# power.net
KiCad netlist of a schematic drawn in Altium Designer
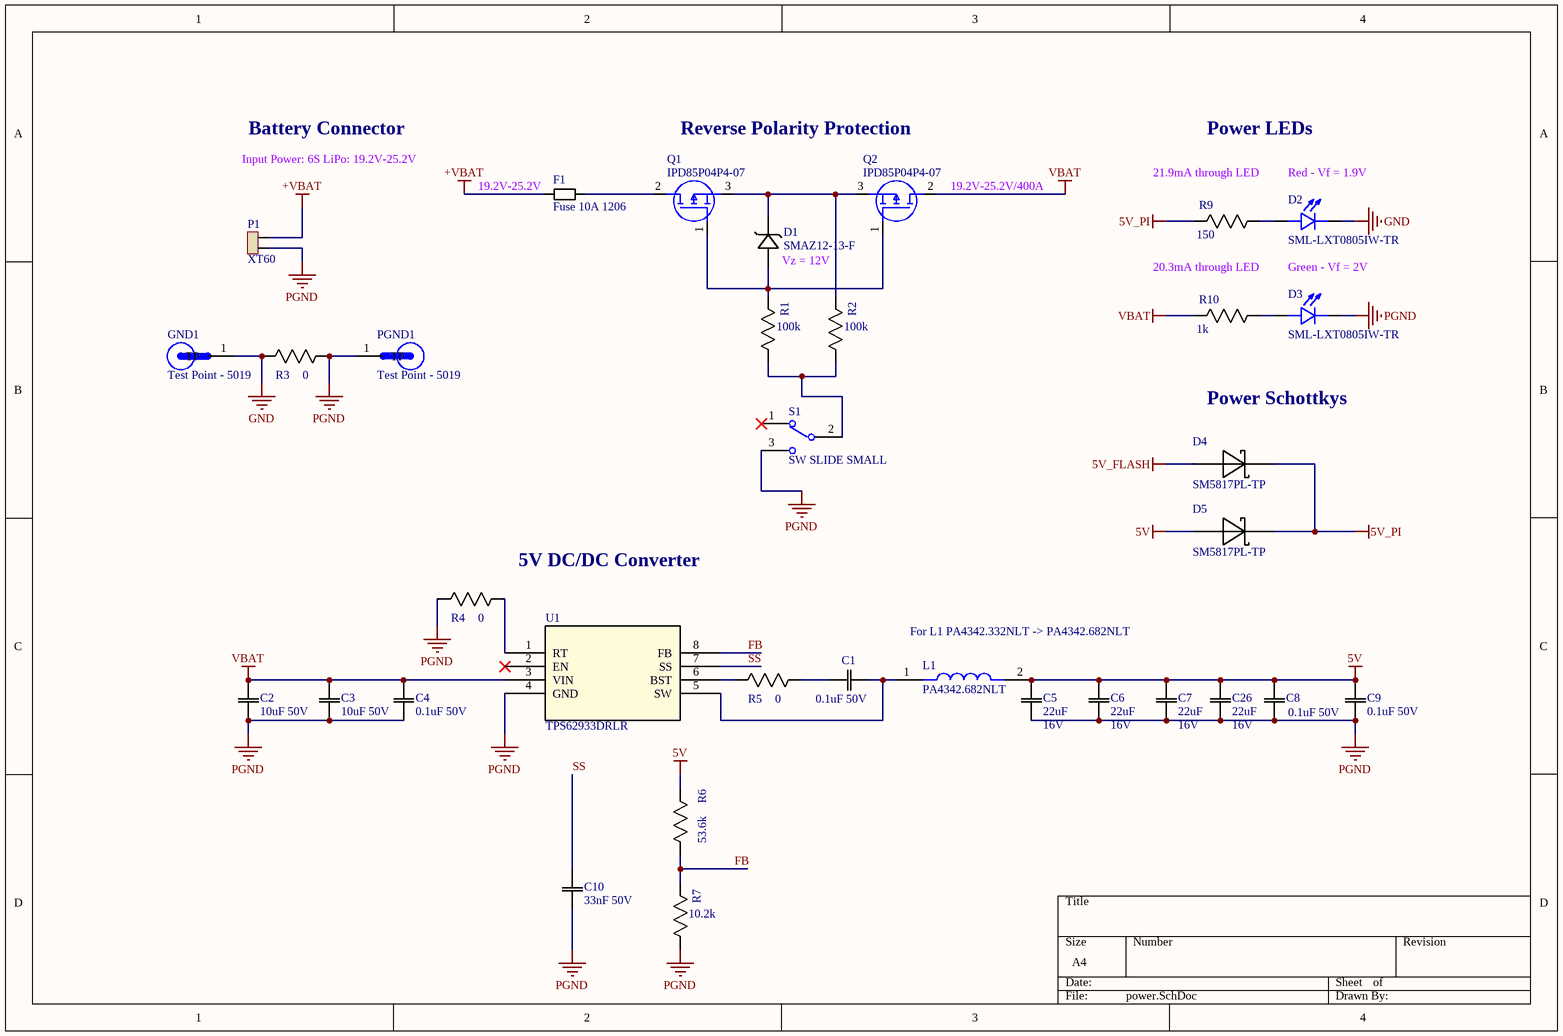
[diagram p0: power.SchDoc]

(export (version "E")
  (design (tool "Eeschema 10.0.6"))
  (components
    (comp (ref "C1")
      (value "0.1uF 50V")
      (footprint "0805")
      (description "Default Symbol for Capacitors")
      (fields (field (name "PART NUMBER") "CAP 10uF 50V") (field (name "TOLERANCE") "10%"))
      (libsource (lib "capacitor_library") (part "CAP_Default"))
    )
    (comp (ref "C2")
      (value "10uF 50V")
      (footprint "0805")
      (description "Default Symbol for Capacitors")
      (fields (field (name "PART NUMBER") "CAP 10uF 50V") (field (name "TOLERANCE") "10%"))
      (libsource (lib "capacitor_library") (part "CAP_Default"))
    )
    (comp (ref "C3")
      (value "10uF 50V")
      (footprint "0805")
      (description "Default Symbol for Capacitors")
      (fields (field (name "PART NUMBER") "CAP 10uF 50V") (field (name "TOLERANCE") "10%"))
      (libsource (lib "capacitor_library") (part "CAP_Default"))
    )
    (comp (ref "C4")
      (value "0.1uF 50V")
      (footprint "0805")
      (description "Default Symbol for Capacitors")
      (fields (field (name "PART NUMBER") "CAP 10uF 50V") (field (name "TOLERANCE") "10%"))
      (libsource (lib "capacitor_library") (part "CAP_Default"))
    )
    (comp (ref "C5")
      (value "22uF")
      (footprint "0805")
      (description "CAP CER 22UF 16V X5R 0805")
      (fields
        (field (name "TOLERANCE") "10%")
        (field (name "RATING") "16V")
        (field (name "PART NUMBER") "CAP 22uF 16V")
      )
      (libsource (lib "capacitor_library") (part "CAP 22uF 16V"))
    )
    (comp (ref "C6")
      (value "22uF")
      (footprint "0805")
      (description "CAP CER 22UF 16V X5R 0805")
      (fields
        (field (name "TOLERANCE") "10%")
        (field (name "RATING") "16V")
        (field (name "PART NUMBER") "CAP 22uF 16V")
      )
      (libsource (lib "capacitor_library") (part "CAP 22uF 16V"))
    )
    (comp (ref "C7")
      (value "22uF")
      (footprint "0805")
      (description "CAP CER 22UF 16V X5R 0805")
      (fields
        (field (name "TOLERANCE") "10%")
        (field (name "RATING") "16V")
        (field (name "PART NUMBER") "CAP 22uF 16V")
      )
      (libsource (lib "capacitor_library") (part "CAP 22uF 16V"))
    )
    (comp (ref "C8")
      (value "0.1uF 50V")
      (footprint "0805")
      (description "Default Symbol for Capacitors")
      (fields (field (name "PART NUMBER") "CAP 10uF 50V") (field (name "TOLERANCE") "10%"))
      (libsource (lib "capacitor_library") (part "CAP_Default"))
    )
    (comp (ref "C9")
      (value "0.1uF 50V")
      (footprint "0805")
      (description "Default Symbol for Capacitors")
      (fields (field (name "PART NUMBER") "CAP 10uF 50V") (field (name "TOLERANCE") "10%"))
      (libsource (lib "capacitor_library") (part "CAP_Default"))
    )
    (comp (ref "C10")
      (value "33nF 50V")
      (footprint "0805")
      (description "Default Symbol for Capacitors")
      (fields (field (name "PART NUMBER") "CAP 33nF 50V") (field (name "TOLERANCE") "5%"))
      (libsource (lib "capacitor_library") (part "CAP_Default"))
    )
    (comp (ref "C26")
      (value "22uF")
      (footprint "0805")
      (description "CAP CER 22UF 16V X5R 0805")
      (fields
        (field (name "TOLERANCE") "10%")
        (field (name "RATING") "16V")
        (field (name "PART NUMBER") "CAP 22uF 16V")
      )
      (libsource (lib "capacitor_library") (part "CAP 22uF 16V"))
    )
    (comp (ref "D1")
      (value "SMAZ12-13-F")
      (footprint "SMA_DIO-L")
      (description "Zener Diode 12 V 1 W ±5% Surface Mount SMA")
      (fields
        (field (name "PART NUMBER") "DIODE ZENER 12V 1W")
        (field (name "COPYRIGHT") "Copyright (C) 2021 Ultra Librarian. All rights reserved.")
      )
      (libsource (lib "Diode_Library") (part "DIODE ZENER 12V 1W"))
    )
    (comp (ref "D2")
      (value "SML-LXT0805IW-TR")
      (footprint "LEDC2012X120N")
      (fields (field (name "MF") "Lumex Opto/Components"))
      (libsource (lib "SML-LXT0805IW-TR") (part "SML-LXT0805IW-TR"))
    )
    (comp (ref "D3")
      (value "SML-LXT0805IW-TR")
      (footprint "LEDC2012X120N")
      (fields (field (name "MF") "Lumex Opto/Components"))
      (libsource (lib "SML-LXT0805IW-TR") (part "SML-LXT0805IW-TR"))
    )
    (comp (ref "D4")
      (value "SM5817PL-TP")
      (footprint "SOD-123")
      (description "Diode Schottky 20V 1A Surface Mount SOD-123FL")
      (fields (field (name "MF") "Micro Commercial Co") (field (name "PART NUMBER") "DIODE SCHOTTKY 20V 1A"))
      (libsource (lib "Diode_Library") (part "DIODE SCHOTTKY 20V 1A"))
    )
    (comp (ref "D5")
      (value "SM5817PL-TP")
      (footprint "SOD-123")
      (description "Diode Schottky 20V 1A Surface Mount SOD-123FL")
      (fields (field (name "MF") "Micro Commercial Co") (field (name "PART NUMBER") "DIODE SCHOTTKY 20V 1A"))
      (libsource (lib "Diode_Library") (part "DIODE SCHOTTKY 20V 1A"))
    )
    (comp (ref "F1")
      (value "Fuse 10A 1206")
      (footprint "1206")
      (description "FUSE 10A 32V AC 63V DC 1206")
      (fields (field (name "PART NUMBER") "FUSE 10A 63V SLOW"))
      (libsource (lib "Fuse_Library") (part "FUSE 10A 63V SLOW"))
    )
    (comp (ref "GND1")
      (value "Test Point - 5019")
      (footprint "TP380X203")
      (description "PC Test Point, Miniature Phosphor Bronze, Silver Plating Surface Mount Mounting Type")
      (fields (field (name "MP") "5019") (field (name "MF") "Keystone Electronics"))
      (libsource (lib "IC_Library") (part "Test Point - 5019"))
    )
    (comp (ref "L1")
      (value "PA4342.682NLT")
      (footprint "IND_PA4342.332NLT")
      (description "FIXED IND 6.8UH 8.5A 23.3MOHM SM")
      (fields (field (name "MF") "Pulse") (field (name "MP") "PA4342.332NLT"))
      (libsource (lib "PA4342.332NLT") (part "PA4342.332NLT"))
    )
    (comp (ref "P1")
      (value "XT60")
      (footprint "Amass_XT60PW-M")
      (description "XT60 CONNECTORS FEMALE PAIR")
      (fields (field (name "MF") "SparkFun Electronics") (field (name "MP") "PRT-10474"))
      (libsource (lib "Connector_Library") (part "XT60 Connector"))
    )
    (comp (ref "PGND1")
      (value "Test Point - 5019")
      (footprint "TP380X203")
      (description "PC Test Point, Miniature Phosphor Bronze, Silver Plating Surface Mount Mounting Type")
      (fields (field (name "MP") "5019") (field (name "MF") "Keystone Electronics"))
      (libsource (lib "IC_Library") (part "Test Point - 5019"))
    )
    (comp (ref "Q1")
      (value "IPD85P04P4-07")
      (footprint "DPAK (TO-252)")
      (description "P-Channel 40 V 85A (Tc) 88W (Tc) Surface Mount PG-TO252-3-313")
      (fields (field (name "PART NUMBER") "MOSFET IPD85P04P4-07"))
      (libsource (lib "Transistor_Library") (part "MOSFET IPD85P04P4-07"))
    )
    (comp (ref "Q2")
      (value "IPD85P04P4-07")
      (footprint "DPAK (TO-252)")
      (description "P-Channel 40 V 85A (Tc) 88W (Tc) Surface Mount PG-TO252-3-313")
      (fields (field (name "PART NUMBER") "MOSFET IPD85P04P4-07"))
      (libsource (lib "Transistor_Library") (part "MOSFET IPD85P04P4-07"))
    )
    (comp (ref "R1")
      (value "100k")
      (footprint "0805")
      (description "Default Resistor Symbol")
      (fields (field (name "TOLERANCE") "1%") (field (name "PART NUMBER") "RES 100k 1/8W - 1%"))
      (libsource (lib "") (part "RES_DEFAULT_1"))
    )
    (comp (ref "R2")
      (value "100k")
      (footprint "0805")
      (description "Default Resistor Symbol")
      (fields (field (name "TOLERANCE") "1%") (field (name "PART NUMBER") "RES 100k 1/8W - 1%"))
      (libsource (lib "") (part "RES_DEFAULT_1"))
    )
    (comp (ref "R3")
      (value "0")
      (footprint "0805")
      (description "Default Resistor Symbol")
      (fields (field (name "PART NUMBER") "RES 0 JUMPER 0603"))
      (libsource (lib "Resistor_Library") (part "RES_DEFAULT"))
    )
    (comp (ref "R4")
      (value "0")
      (footprint "0805")
      (description "Default Resistor Symbol")
      (fields (field (name "PART NUMBER") "RES 0 JUMPER 0603"))
      (libsource (lib "Resistor_Library") (part "RES_DEFAULT"))
    )
    (comp (ref "R5")
      (value "0")
      (footprint "0805")
      (description "Default Resistor Symbol")
      (fields (field (name "PART NUMBER") "RES 0 JUMPER 0603"))
      (libsource (lib "") (part "RES_DEFAULT_1"))
    )
    (comp (ref "R6")
      (value "53.6k")
      (footprint "0805")
      (description "Default Resistor Symbol")
      (fields (field (name "TOLERANCE") "5%") (field (name "PART NUMBER") "RES 56.2k 1/10W"))
      (libsource (lib "") (part "RES_DEFAULT_2"))
    )
    (comp (ref "R7")
      (value "10.2k")
      (footprint "0805")
      (description "Default Resistor Symbol")
      (fields (field (name "TOLERANCE") "5%") (field (name "PART NUMBER") "RES 10.2k 1/8W"))
      (libsource (lib "Resistor_Library") (part "RES_DEFAULT"))
    )
    (comp (ref "R9")
      (value "150")
      (footprint "0805")
      (description "Default Resistor Symbol")
      (fields (field (name "TOLERANCE") "5%") (field (name "PART NUMBER") "RES 150.0 1/8W"))
      (libsource (lib "") (part "RES_DEFAULT_1"))
    )
    (comp (ref "R10")
      (value "1k")
      (footprint "0805")
      (description "Default Resistor Symbol")
      (fields (field (name "TOLERANCE") "5%") (field (name "PART NUMBER") "RES 1.1k 1/8W"))
      (libsource (lib "Resistor_Library") (part "RES_DEFAULT"))
    )
    (comp (ref "S1")
      (value "SW SLIDE SMALL")
      (footprint "SW SLIDE SMALL")
      (description "Slide Switch SPDT Surface Mount, Right Angle")
      (fields (field (name "MF") "C&K") (field (name "MP") "JS102011SAQN"))
      (libsource (lib "Switch_Library") (part "SW SLIDE SMALL"))
    )
    (comp (ref "U1")
      (value "TPS62933DRLR")
      (footprint "SOT_33DRLR_TEX")
      (description "No Description Available")
      (libsource (lib "XTPS62933DRLR") (part "XTPS62933DRLR"))
    )
  )
  (nets
    (net (code "1") (name "+VBAT") (class "Default")
      (node (ref "F1") (pin "1") (pinfunction "1_1") (pintype "passive"))
      (node (ref "P1") (pin "2") (pinfunction "2_2") (pintype "passive"))
    )
    (net (code "2") (name "/FB") (class "Default")
      (node (ref "R6") (pin "1") (pinfunction "R1_1") (pintype "passive"))
      (node (ref "R7") (pin "2") (pinfunction "R2_2") (pintype "passive"))
      (node (ref "U1") (pin "8") (pinfunction "FB_8") (pintype "passive"))
    )
    (net (code "3") (name "/SS") (class "Default")
      (node (ref "C10") (pin "2") (pinfunction "C2_2") (pintype "passive"))
      (node (ref "U1") (pin "7") (pinfunction "SS_7") (pintype "passive"))
    )
    (net (code "4") (name "5V") (class "Default")
      (node (ref "C26") (pin "2") (pinfunction "C2_2") (pintype "passive"))
      (node (ref "C5") (pin "2") (pinfunction "C2_2") (pintype "passive"))
      (node (ref "C6") (pin "2") (pinfunction "C2_2") (pintype "passive"))
      (node (ref "C7") (pin "2") (pinfunction "C2_2") (pintype "passive"))
      (node (ref "C8") (pin "2") (pinfunction "C2_2") (pintype "passive"))
      (node (ref "C9") (pin "2") (pinfunction "C2_2") (pintype "passive"))
      (node (ref "D5") (pin "A") (pinfunction "A_A") (pintype "passive"))
      (node (ref "L1") (pin "2") (pinfunction "2_2") (pintype "passive"))
      (node (ref "R6") (pin "2") (pinfunction "R2_2") (pintype "passive"))
    )
    (net (code "5") (name "5V_FLASH") (class "Default")
      (node (ref "D4") (pin "A") (pinfunction "A_A") (pintype "passive"))
    )
    (net (code "6") (name "5V_PI") (class "Default")
      (node (ref "D4") (pin "C") (pinfunction "K_C") (pintype "passive"))
      (node (ref "D5") (pin "C") (pinfunction "K_C") (pintype "passive"))
      (node (ref "R9") (pin "2") (pinfunction "R2_2") (pintype "passive"))
    )
    (net (code "7") (name "GND") (class "Default")
      (node (ref "D2") (pin "C") (pinfunction "C_C") (pintype "passive"))
      (node (ref "GND1") (pin "1") (pinfunction "TP_1") (pintype "passive"))
      (node (ref "R3") (pin "2") (pinfunction "R2_2") (pintype "passive"))
    )
    (net (code "8") (name "Net-(C1-C1)") (class "Default")
      (node (ref "C1") (pin "1") (pinfunction "C1_1") (pintype "passive"))
      (node (ref "L1") (pin "1") (pinfunction "1_1") (pintype "passive"))
      (node (ref "U1") (pin "5") (pinfunction "SW_5") (pintype "passive"))
    )
    (net (code "9") (name "Net-(C1-C2)") (class "Default")
      (node (ref "C1") (pin "2") (pinfunction "C2_2") (pintype "passive"))
      (node (ref "R5") (pin "1") (pinfunction "R1_1") (pintype "passive"))
    )
    (net (code "10") (name "Net-(Q1-D)") (class "Default")
      (node (ref "F1") (pin "2") (pinfunction "2_2") (pintype "passive"))
      (node (ref "Q1") (pin "2") (pinfunction "D_2") (pintype "passive"))
    )
    (net (code "11") (name "Net-(Q1-G)") (class "Default")
      (node (ref "D1") (pin "2") (pinfunction "2_2") (pintype "passive"))
      (node (ref "Q1") (pin "1") (pinfunction "G_1") (pintype "passive"))
      (node (ref "Q2") (pin "1") (pinfunction "G_1") (pintype "passive"))
      (node (ref "R1") (pin "2") (pinfunction "R2_2") (pintype "passive"))
    )
    (net (code "12") (name "Net-(Q1-S)") (class "Default")
      (node (ref "D1") (pin "1") (pinfunction "1_1") (pintype "passive"))
      (node (ref "Q1") (pin "3") (pinfunction "S_3") (pintype "passive"))
      (node (ref "Q2") (pin "3") (pinfunction "S_3") (pintype "passive"))
      (node (ref "R2") (pin "2") (pinfunction "R2_2") (pintype "passive"))
    )
    (net (code "13") (name "Net-(R1-R1)") (class "Default")
      (node (ref "R1") (pin "1") (pinfunction "R1_1") (pintype "passive"))
      (node (ref "R2") (pin "1") (pinfunction "R1_1") (pintype "passive"))
      (node (ref "S1") (pin "2") (pinfunction "2_2") (pintype "passive"))
    )
    (net (code "14") (name "Net-(R4-R1)") (class "Default")
      (node (ref "R4") (pin "1") (pinfunction "R1_1") (pintype "passive"))
      (node (ref "U1") (pin "1") (pinfunction "RT_1") (pintype "passive"))
    )
    (net (code "15") (name "Net-(R5-R2)") (class "Default")
      (node (ref "R5") (pin "2") (pinfunction "R2_2") (pintype "passive"))
      (node (ref "U1") (pin "6") (pinfunction "BST_6") (pintype "passive"))
    )
    (net (code "16") (name "Net-(R9-R1)") (class "Default")
      (node (ref "D2") (pin "A") (pinfunction "A_A") (pintype "passive"))
      (node (ref "R9") (pin "1") (pinfunction "R1_1") (pintype "passive"))
    )
    (net (code "17") (name "Net-(R10-R1)") (class "Default")
      (node (ref "D3") (pin "A") (pinfunction "A_A") (pintype "passive"))
      (node (ref "R10") (pin "1") (pinfunction "R1_1") (pintype "passive"))
    )
    (net (code "18") (name "PGND") (class "Default")
      (node (ref "C10") (pin "1") (pinfunction "C1_1") (pintype "passive"))
      (node (ref "C2") (pin "1") (pinfunction "C1_1") (pintype "passive"))
      (node (ref "C26") (pin "1") (pinfunction "C1_1") (pintype "passive"))
      (node (ref "C3") (pin "1") (pinfunction "C1_1") (pintype "passive"))
      (node (ref "C4") (pin "1") (pinfunction "C1_1") (pintype "passive"))
      (node (ref "C5") (pin "1") (pinfunction "C1_1") (pintype "passive"))
      (node (ref "C6") (pin "1") (pinfunction "C1_1") (pintype "passive"))
      (node (ref "C7") (pin "1") (pinfunction "C1_1") (pintype "passive"))
      (node (ref "C8") (pin "1") (pinfunction "C1_1") (pintype "passive"))
      (node (ref "C9") (pin "1") (pinfunction "C1_1") (pintype "passive"))
      (node (ref "D3") (pin "C") (pinfunction "C_C") (pintype "passive"))
      (node (ref "P1") (pin "1") (pinfunction "1_1") (pintype "passive"))
      (node (ref "PGND1") (pin "1") (pinfunction "TP_1") (pintype "passive"))
      (node (ref "R3") (pin "1") (pinfunction "R1_1") (pintype "passive"))
      (node (ref "R4") (pin "2") (pinfunction "R2_2") (pintype "passive"))
      (node (ref "R7") (pin "1") (pinfunction "R1_1") (pintype "passive"))
      (node (ref "S1") (pin "3") (pinfunction "3_3") (pintype "passive"))
      (node (ref "U1") (pin "4") (pinfunction "GND_4") (pintype "power_in"))
    )
    (net (code "19") (name "VBAT") (class "Default")
      (node (ref "C2") (pin "2") (pinfunction "C2_2") (pintype "passive"))
      (node (ref "C3") (pin "2") (pinfunction "C2_2") (pintype "passive"))
      (node (ref "C4") (pin "2") (pinfunction "C2_2") (pintype "passive"))
      (node (ref "Q2") (pin "2") (pinfunction "D_2") (pintype "passive"))
      (node (ref "R10") (pin "2") (pinfunction "R2_2") (pintype "passive"))
      (node (ref "U1") (pin "3") (pinfunction "VIN_3") (pintype "passive"))
    )
    (net (code "20") (name "unconnected-(S1-Pad1)") (class "Default")
      (node (ref "S1") (pin "1") (pinfunction "1_1") (pintype "passive+no_connect"))
    )
    (net (code "21") (name "unconnected-(U1-EN-Pad2)") (class "Default")
      (node (ref "U1") (pin "2") (pinfunction "EN_2") (pintype "passive+no_connect"))
    )
  )
)
